# FPGA_B34.net
KiCad netlist of a schematic drawn in Altium Designer
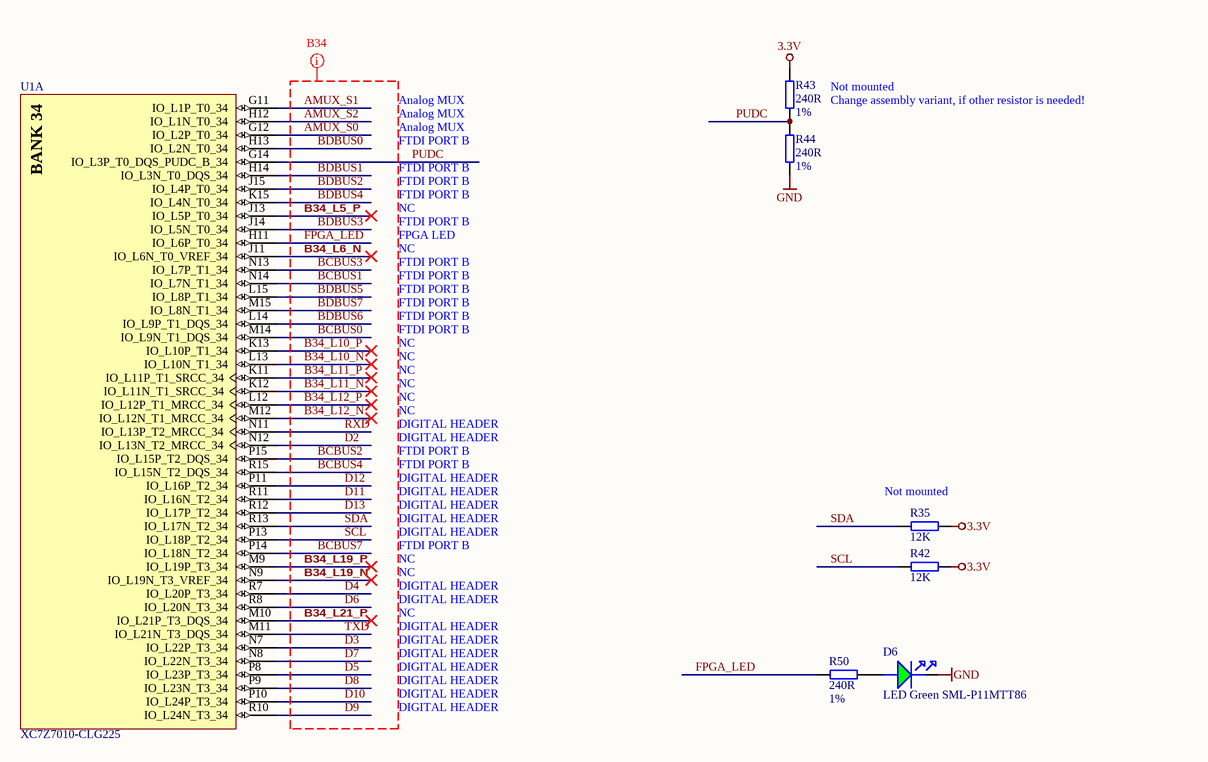
[diagram p0: FPGA_B34.SchDoc]

(export (version "E")
  (design (tool "Eeschema 10.0.6"))
  (components
    (comp (ref "D6")
      (value "LED Green SML-P11MTT86")
      (footprint "LEDC1006X25N_GREEN")
      (description "LED Grün SML-P11MTT86 SMD")
      (libsource (lib "TE") (part "LED_GRUEN"))
    )
    (comp (ref "R35")
      (value "12K")
      (footprint "RESC1005X40N")
      (description "WID SMD 12K 1% 0,063W")
      (libsource (lib "TE") (part "RES"))
    )
    (comp (ref "R42")
      (value "12K")
      (footprint "RESC1005X40N")
      (description "WID SMD 12K 1% 0,063W")
      (libsource (lib "TE") (part "RES"))
    )
    (comp (ref "R43")
      (value "240R")
      (footprint "RESC1005X40N")
      (description "WID SMD 240R 1% 0,063W")
      (fields (field (name "TOLERANCE") "1%"))
      (libsource (lib "TE") (part "RES"))
    )
    (comp (ref "R44")
      (value "240R")
      (footprint "RESC1005X40N")
      (description "WID SMD 240R 1% 0,063W")
      (fields (field (name "TOLERANCE") "1%"))
      (libsource (lib "TE") (part "RES"))
    )
    (comp (ref "R50")
      (value "240R")
      (footprint "RESC1005X40N")
      (description "WID SMD 240R 1% 0,063W")
      (fields (field (name "TOLERANCE") "1%"))
      (libsource (lib "TE") (part "RES"))
    )
    (comp (ref "U1") (value "XC7Z7010-CLG225") (libsource (lib "XC7Z010-CLG225") (part "XC7Z7010-CLG225")))
  )
  (nets
    (net (code "1") (name "/AMUX_S0") (class "Default")
      (node (ref "U1") (pin "G12") (pinfunction "IO_L2P_T0_34_G12") (pintype "bidirectional"))
    )
    (net (code "2") (name "/AMUX_S1") (class "Default")
      (node (ref "U1") (pin "G11") (pinfunction "IO_L1P_T0_34_G11") (pintype "bidirectional"))
    )
    (net (code "3") (name "/AMUX_S2") (class "Default")
      (node (ref "U1") (pin "H12") (pinfunction "IO_L1N_T0_34_H12") (pintype "bidirectional"))
    )
    (net (code "4") (name "/B34_L5_P") (class "Default")
      (node (ref "U1") (pin "J13") (pinfunction "IO_L5P_T0_34_J13") (pintype "bidirectional+no_connect"))
    )
    (net (code "5") (name "/B34_L6_N") (class "Default")
      (node (ref "U1") (pin "J11") (pinfunction "IO_L6N_T0_VREF_34_J11") (pintype "bidirectional+no_connect"))
    )
    (net (code "6") (name "/B34_L10_N") (class "Default")
      (node (ref "U1") (pin "L13") (pinfunction "IO_L10N_T1_34_L13") (pintype "bidirectional+no_connect"))
    )
    (net (code "7") (name "/B34_L10_P") (class "Default")
      (node (ref "U1") (pin "K13") (pinfunction "IO_L10P_T1_34_K13") (pintype "bidirectional+no_connect"))
    )
    (net (code "8") (name "/B34_L11_N") (class "Default")
      (node (ref "U1") (pin "K12") (pinfunction "IO_L11N_T1_SRCC_34_K12") (pintype "bidirectional+no_connect"))
    )
    (net (code "9") (name "/B34_L11_P") (class "Default")
      (node (ref "U1") (pin "K11") (pinfunction "IO_L11P_T1_SRCC_34_K11") (pintype "bidirectional+no_connect"))
    )
    (net (code "10") (name "/B34_L12_N") (class "Default")
      (node (ref "U1") (pin "M12") (pinfunction "IO_L12N_T1_MRCC_34_M12") (pintype "bidirectional+no_connect"))
    )
    (net (code "11") (name "/B34_L12_P") (class "Default")
      (node (ref "U1") (pin "L12") (pinfunction "IO_L12P_T1_MRCC_34_L12") (pintype "bidirectional+no_connect"))
    )
    (net (code "12") (name "/B34_L19_N") (class "Default")
      (node (ref "U1") (pin "N9") (pinfunction "IO_L19N_T3_VREF_34_N9") (pintype "bidirectional+no_connect"))
    )
    (net (code "13") (name "/B34_L19_P") (class "Default")
      (node (ref "U1") (pin "M9") (pinfunction "IO_L19P_T3_34_M9") (pintype "bidirectional+no_connect"))
    )
    (net (code "14") (name "/B34_L21_P") (class "Default")
      (node (ref "U1") (pin "M10") (pinfunction "IO_L21P_T3_DQS_34_M10") (pintype "bidirectional+no_connect"))
    )
    (net (code "15") (name "/BCBUS0") (class "Default")
      (node (ref "U1") (pin "M14") (pinfunction "IO_L9N_T1_DQS_34_M14") (pintype "bidirectional"))
    )
    (net (code "16") (name "/BCBUS1") (class "Default")
      (node (ref "U1") (pin "N14") (pinfunction "IO_L7N_T1_34_N14") (pintype "bidirectional"))
    )
    (net (code "17") (name "/BCBUS2") (class "Default")
      (node (ref "U1") (pin "P15") (pinfunction "IO_L15P_T2_DQS_34_P15") (pintype "bidirectional"))
    )
    (net (code "18") (name "/BCBUS3") (class "Default")
      (node (ref "U1") (pin "N13") (pinfunction "IO_L7P_T1_34_N13") (pintype "bidirectional"))
    )
    (net (code "19") (name "/BCBUS4") (class "Default")
      (node (ref "U1") (pin "R15") (pinfunction "IO_L15N_T2_DQS_34_R15") (pintype "bidirectional"))
    )
    (net (code "20") (name "/BCBUS7") (class "Default")
      (node (ref "U1") (pin "P14") (pinfunction "IO_L18N_T2_34_P14") (pintype "bidirectional"))
    )
    (net (code "21") (name "/BDBUS0") (class "Default")
      (node (ref "U1") (pin "H13") (pinfunction "IO_L2N_T0_34_H13") (pintype "bidirectional"))
    )
    (net (code "22") (name "/BDBUS1") (class "Default")
      (node (ref "U1") (pin "H14") (pinfunction "IO_L3N_T0_DQS_34_H14") (pintype "bidirectional"))
    )
    (net (code "23") (name "/BDBUS2") (class "Default")
      (node (ref "U1") (pin "J15") (pinfunction "IO_L4P_T0_34_J15") (pintype "bidirectional"))
    )
    (net (code "24") (name "/BDBUS3") (class "Default")
      (node (ref "U1") (pin "J14") (pinfunction "IO_L5N_T0_34_J14") (pintype "bidirectional"))
    )
    (net (code "25") (name "/BDBUS4") (class "Default")
      (node (ref "U1") (pin "K15") (pinfunction "IO_L4N_T0_34_K15") (pintype "bidirectional"))
    )
    (net (code "26") (name "/BDBUS5") (class "Default")
      (node (ref "U1") (pin "L15") (pinfunction "IO_L8P_T1_34_L15") (pintype "bidirectional"))
    )
    (net (code "27") (name "/BDBUS6") (class "Default")
      (node (ref "U1") (pin "L14") (pinfunction "IO_L9P_T1_DQS_34_L14") (pintype "bidirectional"))
    )
    (net (code "28") (name "/BDBUS7") (class "Default")
      (node (ref "U1") (pin "M15") (pinfunction "IO_L8N_T1_34_M15") (pintype "bidirectional"))
    )
    (net (code "29") (name "/D2") (class "Default")
      (node (ref "U1") (pin "N12") (pinfunction "IO_L13N_T2_MRCC_34_N12") (pintype "bidirectional"))
    )
    (net (code "30") (name "/D3") (class "Default")
      (node (ref "U1") (pin "N7") (pinfunction "IO_L22P_T3_34_N7") (pintype "bidirectional"))
    )
    (net (code "31") (name "/D4") (class "Default")
      (node (ref "U1") (pin "R7") (pinfunction "IO_L20P_T3_34_R7") (pintype "bidirectional"))
    )
    (net (code "32") (name "/D5") (class "Default")
      (node (ref "U1") (pin "P8") (pinfunction "IO_L23P_T3_34_P8") (pintype "bidirectional"))
    )
    (net (code "33") (name "/D6") (class "Default")
      (node (ref "U1") (pin "R8") (pinfunction "IO_L20N_T3_34_R8") (pintype "bidirectional"))
    )
    (net (code "34") (name "/D7") (class "Default")
      (node (ref "U1") (pin "N8") (pinfunction "IO_L22N_T3_34_N8") (pintype "bidirectional"))
    )
    (net (code "35") (name "/D8") (class "Default")
      (node (ref "U1") (pin "P9") (pinfunction "IO_L23N_T3_34_P9") (pintype "bidirectional"))
    )
    (net (code "36") (name "/D9") (class "Default")
      (node (ref "U1") (pin "R10") (pinfunction "IO_L24N_T3_34_R10") (pintype "bidirectional"))
    )
    (net (code "37") (name "/D10") (class "Default")
      (node (ref "U1") (pin "P10") (pinfunction "IO_L24P_T3_34_P10") (pintype "bidirectional"))
    )
    (net (code "38") (name "/D11") (class "Default")
      (node (ref "U1") (pin "R11") (pinfunction "IO_L16N_T2_34_R11") (pintype "bidirectional"))
    )
    (net (code "39") (name "/D12") (class "Default")
      (node (ref "U1") (pin "P11") (pinfunction "IO_L16P_T2_34_P11") (pintype "bidirectional"))
    )
    (net (code "40") (name "/D13") (class "Default")
      (node (ref "U1") (pin "R12") (pinfunction "IO_L17P_T2_34_R12") (pintype "bidirectional"))
    )
    (net (code "41") (name "/FPGA_LED") (class "Default")
      (node (ref "R50") (pin "2") (pinfunction "2_2") (pintype "passive"))
      (node (ref "U1") (pin "H11") (pinfunction "IO_L6P_T0_34_H11") (pintype "bidirectional"))
    )
    (net (code "42") (name "/PUDC") (class "Default")
      (node (ref "R43") (pin "2") (pinfunction "2_2") (pintype "passive"))
      (node (ref "R44") (pin "1") (pinfunction "1_1") (pintype "passive"))
      (node (ref "U1") (pin "G14") (pinfunction "IO_L3P_T0_DQS_PUDC_B_34_G14") (pintype "bidirectional"))
    )
    (net (code "43") (name "/RXD") (class "Default")
      (node (ref "U1") (pin "N11") (pinfunction "IO_L13P_T2_MRCC_34_N11") (pintype "bidirectional"))
    )
    (net (code "44") (name "/SCL") (class "Default")
      (node (ref "R42") (pin "1") (pinfunction "1_1") (pintype "passive"))
      (node (ref "U1") (pin "P13") (pinfunction "IO_L18P_T2_34_P13") (pintype "bidirectional"))
    )
    (net (code "45") (name "/SDA") (class "Default")
      (node (ref "R35") (pin "1") (pinfunction "1_1") (pintype "passive"))
      (node (ref "U1") (pin "R13") (pinfunction "IO_L17N_T2_34_R13") (pintype "bidirectional"))
    )
    (net (code "46") (name "/TXD") (class "Default")
      (node (ref "U1") (pin "M11") (pinfunction "IO_L21N_T3_DQS_34_M11") (pintype "bidirectional"))
    )
    (net (code "47") (name "3.3V") (class "Default")
      (node (ref "R35") (pin "2") (pinfunction "2_2") (pintype "passive"))
      (node (ref "R42") (pin "2") (pinfunction "2_2") (pintype "passive"))
      (node (ref "R43") (pin "1") (pinfunction "1_1") (pintype "passive"))
    )
    (net (code "48") (name "GND") (class "Default")
      (node (ref "D6") (pin "K") (pinfunction "K_K") (pintype "passive"))
      (node (ref "R44") (pin "2") (pinfunction "2_2") (pintype "passive"))
    )
    (net (code "49") (name "Net-(D6-PadA)") (class "Default")
      (node (ref "D6") (pin "A") (pinfunction "A_A") (pintype "passive"))
      (node (ref "R50") (pin "1") (pinfunction "1_1") (pintype "passive"))
    )
  )
)
